# Riego_Auto_V1_0.net
KiCad netlist of a schematic drawn in EAGLE
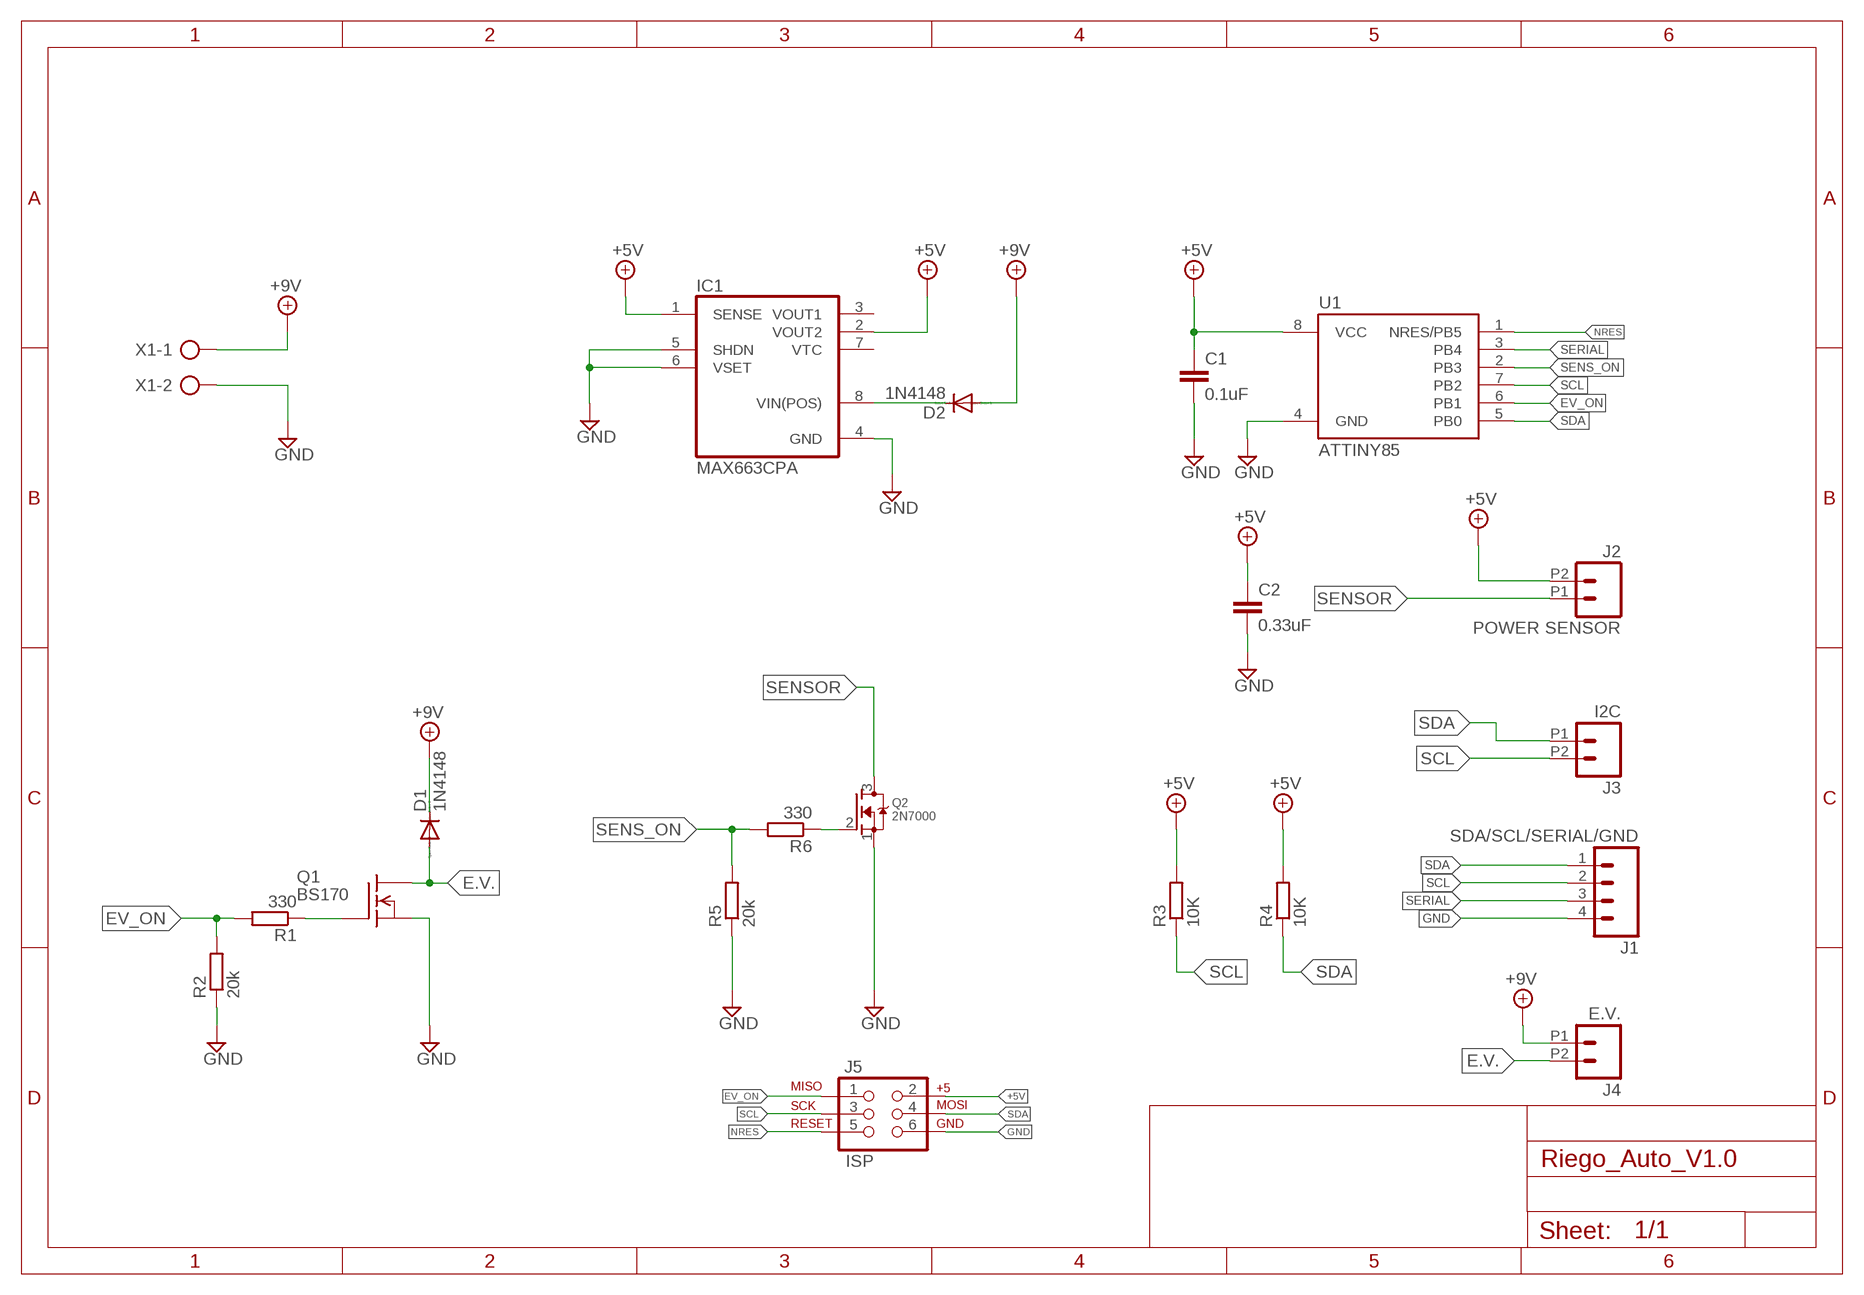
[diagram p0: schematic, sheet 1]

(export (version "E")
  (design (tool "Eeschema 10.0.6"))
  (components
    (comp (ref "C1")
      (value "0.1uF")
      (footprint "eagle-import:C050-025X075")
      (libsource (lib "eagle-import") (part "C-EU050-025X075"))
    )
    (comp (ref "C2")
      (value "0.33uF")
      (footprint "eagle-import:C050-024X044")
      (libsource (lib "eagle-import") (part "C-EU050-024X044"))
    )
    (comp (ref "D1")
      (value "1N4148")
      (footprint "eagle-import:DO35-7")
      (libsource (lib "eagle-import") (part "1N4148DO35-7"))
    )
    (comp (ref "D2")
      (value "1N4148")
      (footprint "eagle-import:DO35-7")
      (libsource (lib "eagle-import") (part "1N4148DO35-7"))
    )
    (comp (ref "IC1")
      (value "MAX663CPA")
      (footprint "eagle-import:DIL08")
      (fields (field (name "MPN") "MAX663CPA+"))
      (libsource (lib "eagle-import") (part "MAX663CPA"))
    )
    (comp (ref "J1")
      (value "SDA/SCL/SERIAL/GND")
      (footprint "eagle-import:1X04")
      (libsource (lib "eagle-import") (part "M04PTH"))
    )
    (comp (ref "J2")
      (value "POWER SENSOR")
      (footprint "eagle-import:1X02_2.54_SCREWTERM")
      (libsource (lib "eagle-import") (part "M022.54MM_SCREWTERM"))
    )
    (comp (ref "J3")
      (value "I2C")
      (footprint "eagle-import:1X02_2.54_SCREWTERM")
      (libsource (lib "eagle-import") (part "M022.54MM_SCREWTERM"))
    )
    (comp (ref "J4")
      (value "E.V.")
      (footprint "eagle-import:1X02_2.54_SCREWTERM")
      (libsource (lib "eagle-import") (part "M022.54MM_SCREWTERM"))
    )
    (comp (ref "J5")
      (value "ISP")
      (footprint "eagle-import:2X3")
      (libsource (lib "eagle-import") (part "AVR_SPI_PRG_6PTH"))
    )
    (comp (ref "Q1")
      (value "BS170")
      (footprint "eagle-import:TO92-INLINE")
      (libsource (lib "eagle-import") (part "FQN1N50CI"))
    )
    (comp (ref "Q2")
      (value "2N7000")
      (footprint "eagle-import:TO92-INLINE")
      (libsource (lib "eagle-import") (part "MOSFET-N"))
    )
    (comp (ref "R1")
      (value "330")
      (footprint "eagle-import:0204_7")
      (libsource (lib "eagle-import") (part "R-EU_0204/7"))
    )
    (comp (ref "R2")
      (value "20k")
      (footprint "eagle-import:0204_7")
      (libsource (lib "eagle-import") (part "R-EU_0204/7"))
    )
    (comp (ref "R3")
      (value "10K")
      (footprint "eagle-import:0204_7")
      (libsource (lib "eagle-import") (part "R-EU_0204/7"))
    )
    (comp (ref "R4")
      (value "10K")
      (footprint "eagle-import:0204_7")
      (libsource (lib "eagle-import") (part "R-EU_0204/7"))
    )
    (comp (ref "R5")
      (value "20k")
      (footprint "eagle-import:0204_7")
      (libsource (lib "eagle-import") (part "R-EU_0204/7"))
    )
    (comp (ref "R6")
      (value "330")
      (footprint "eagle-import:0204_7")
      (libsource (lib "eagle-import") (part "R-EU_0204/7"))
    )
    (comp (ref "U1")
      (value "ATTINY85")
      (footprint "eagle-import:DIL08")
      (libsource (lib "eagle-import") (part "ATTINY85DIL"))
    )
    (comp (ref "X1")
      (value "AK500/2")
      (footprint "eagle-import:AK500_2")
      (libsource (lib "eagle-import") (part "AK500/2"))
    )
  )
  (nets
    (net (code "1") (name "+5V") (class "Default")
      (node (ref "C1") (pin "1") (pinfunction "1_1") (pintype "passive"))
      (node (ref "C2") (pin "1") (pinfunction "1_1") (pintype "passive"))
      (node (ref "IC1") (pin "1") (pinfunction "SENSE_1") (pintype "input"))
      (node (ref "IC1") (pin "2") (pinfunction "VOUT2_2") (pintype "output"))
      (node (ref "J2") (pin "P2") (pinfunction "2_P2") (pintype "passive"))
      (node (ref "J5") (pin "2") (pinfunction "2_2") (pintype "passive"))
      (node (ref "R3") (pin "2") (pinfunction "2_2") (pintype "passive"))
      (node (ref "R4") (pin "2") (pinfunction "2_2") (pintype "passive"))
      (node (ref "U1") (pin "8") (pinfunction "VCC_8") (pintype "power_in"))
    )
    (net (code "2") (name "+9V") (class "Default")
      (node (ref "D1") (pin "C") (pinfunction "C_C") (pintype "passive"))
      (node (ref "D2") (pin "A") (pinfunction "A_A") (pintype "passive"))
      (node (ref "J4") (pin "P1") (pinfunction "1_P1") (pintype "passive"))
      (node (ref "X1") (pin "1") (pinfunction "KL_1") (pintype "passive"))
    )
    (net (code "3") (name "E.V.") (class "Default")
      (node (ref "D1") (pin "A") (pinfunction "A_A") (pintype "passive"))
      (node (ref "J4") (pin "P2") (pinfunction "2_P2") (pintype "passive"))
      (node (ref "Q1") (pin "1") (pinfunction "D_1") (pintype "passive"))
    )
    (net (code "4") (name "EV_ON") (class "Default")
      (node (ref "J5") (pin "1") (pinfunction "1_1") (pintype "passive"))
      (node (ref "R1") (pin "2") (pinfunction "2_2") (pintype "passive"))
      (node (ref "R2") (pin "2") (pinfunction "2_2") (pintype "passive"))
      (node (ref "U1") (pin "6") (pinfunction "PB1_6") (pintype "bidirectional"))
    )
    (net (code "5") (name "GND") (class "Default")
      (node (ref "C1") (pin "2") (pinfunction "2_2") (pintype "passive"))
      (node (ref "C2") (pin "2") (pinfunction "2_2") (pintype "passive"))
      (node (ref "IC1") (pin "4") (pinfunction "GND_4") (pintype "power_in"))
      (node (ref "IC1") (pin "5") (pinfunction "SHDN_5") (pintype "input"))
      (node (ref "IC1") (pin "6") (pinfunction "VSET_6") (pintype "input"))
      (node (ref "J1") (pin "4") (pinfunction "4_4") (pintype "passive"))
      (node (ref "J5") (pin "6") (pinfunction "6_6") (pintype "passive"))
      (node (ref "Q1") (pin "3") (pinfunction "S_3") (pintype "passive"))
      (node (ref "Q2") (pin "1") (pinfunction "S_1") (pintype "bidirectional"))
      (node (ref "R2") (pin "1") (pinfunction "1_1") (pintype "passive"))
      (node (ref "R5") (pin "1") (pinfunction "1_1") (pintype "passive"))
      (node (ref "U1") (pin "4") (pinfunction "GND_4") (pintype "power_in"))
      (node (ref "X1") (pin "2") (pinfunction "KL_2") (pintype "passive"))
    )
    (net (code "6") (name "NRES") (class "Default")
      (node (ref "J5") (pin "5") (pinfunction "5_5") (pintype "passive"))
      (node (ref "U1") (pin "1") (pinfunction "NRES/PB5_1") (pintype "bidirectional"))
    )
    (net (code "7") (name "Net-(IC1-VIN(POS))") (class "Default")
      (node (ref "D2") (pin "C") (pinfunction "C_C") (pintype "passive"))
      (node (ref "IC1") (pin "8") (pinfunction "VIN(POS)_8") (pintype "power_in"))
    )
    (net (code "8") (name "Net-(Q1-G)") (class "Default")
      (node (ref "Q1") (pin "2") (pinfunction "G_2") (pintype "passive"))
      (node (ref "R1") (pin "1") (pinfunction "1_1") (pintype "passive"))
    )
    (net (code "9") (name "Net-(Q2-G)") (class "Default")
      (node (ref "Q2") (pin "2") (pinfunction "G_2") (pintype "bidirectional"))
      (node (ref "R6") (pin "1") (pinfunction "1_1") (pintype "passive"))
    )
    (net (code "10") (name "SCL") (class "Default")
      (node (ref "J1") (pin "2") (pinfunction "2_2") (pintype "passive"))
      (node (ref "J3") (pin "P2") (pinfunction "2_P2") (pintype "passive"))
      (node (ref "J5") (pin "3") (pinfunction "3_3") (pintype "passive"))
      (node (ref "R3") (pin "1") (pinfunction "1_1") (pintype "passive"))
      (node (ref "U1") (pin "7") (pinfunction "PB2_7") (pintype "bidirectional"))
    )
    (net (code "11") (name "SDA") (class "Default")
      (node (ref "J1") (pin "1") (pinfunction "1_1") (pintype "passive"))
      (node (ref "J3") (pin "P1") (pinfunction "1_P1") (pintype "passive"))
      (node (ref "J5") (pin "4") (pinfunction "4_4") (pintype "passive"))
      (node (ref "R4") (pin "1") (pinfunction "1_1") (pintype "passive"))
      (node (ref "U1") (pin "5") (pinfunction "PB0_5") (pintype "bidirectional"))
    )
    (net (code "12") (name "SENSOR") (class "Default")
      (node (ref "J2") (pin "P1") (pinfunction "1_P1") (pintype "passive"))
      (node (ref "Q2") (pin "3") (pinfunction "D_3") (pintype "bidirectional"))
    )
    (net (code "13") (name "SENS_ON") (class "Default")
      (node (ref "R5") (pin "2") (pinfunction "2_2") (pintype "passive"))
      (node (ref "R6") (pin "2") (pinfunction "2_2") (pintype "passive"))
      (node (ref "U1") (pin "2") (pinfunction "PB3_2") (pintype "bidirectional"))
    )
    (net (code "14") (name "SERIAL") (class "Default")
      (node (ref "J1") (pin "3") (pinfunction "3_3") (pintype "passive"))
      (node (ref "U1") (pin "3") (pinfunction "PB4_3") (pintype "bidirectional"))
    )
    (net (code "15") (name "unconnected-(IC1-VOUT1-Pad3)") (class "Default")
      (node (ref "IC1") (pin "3") (pinfunction "VOUT1_3") (pintype "output"))
    )
    (net (code "16") (name "unconnected-(IC1-VTC-Pad7)") (class "Default")
      (node (ref "IC1") (pin "7") (pinfunction "VTC_7") (pintype "output"))
    )
  )
)
